# dynacomp.net
KiCad netlist of a schematic drawn in EAGLE
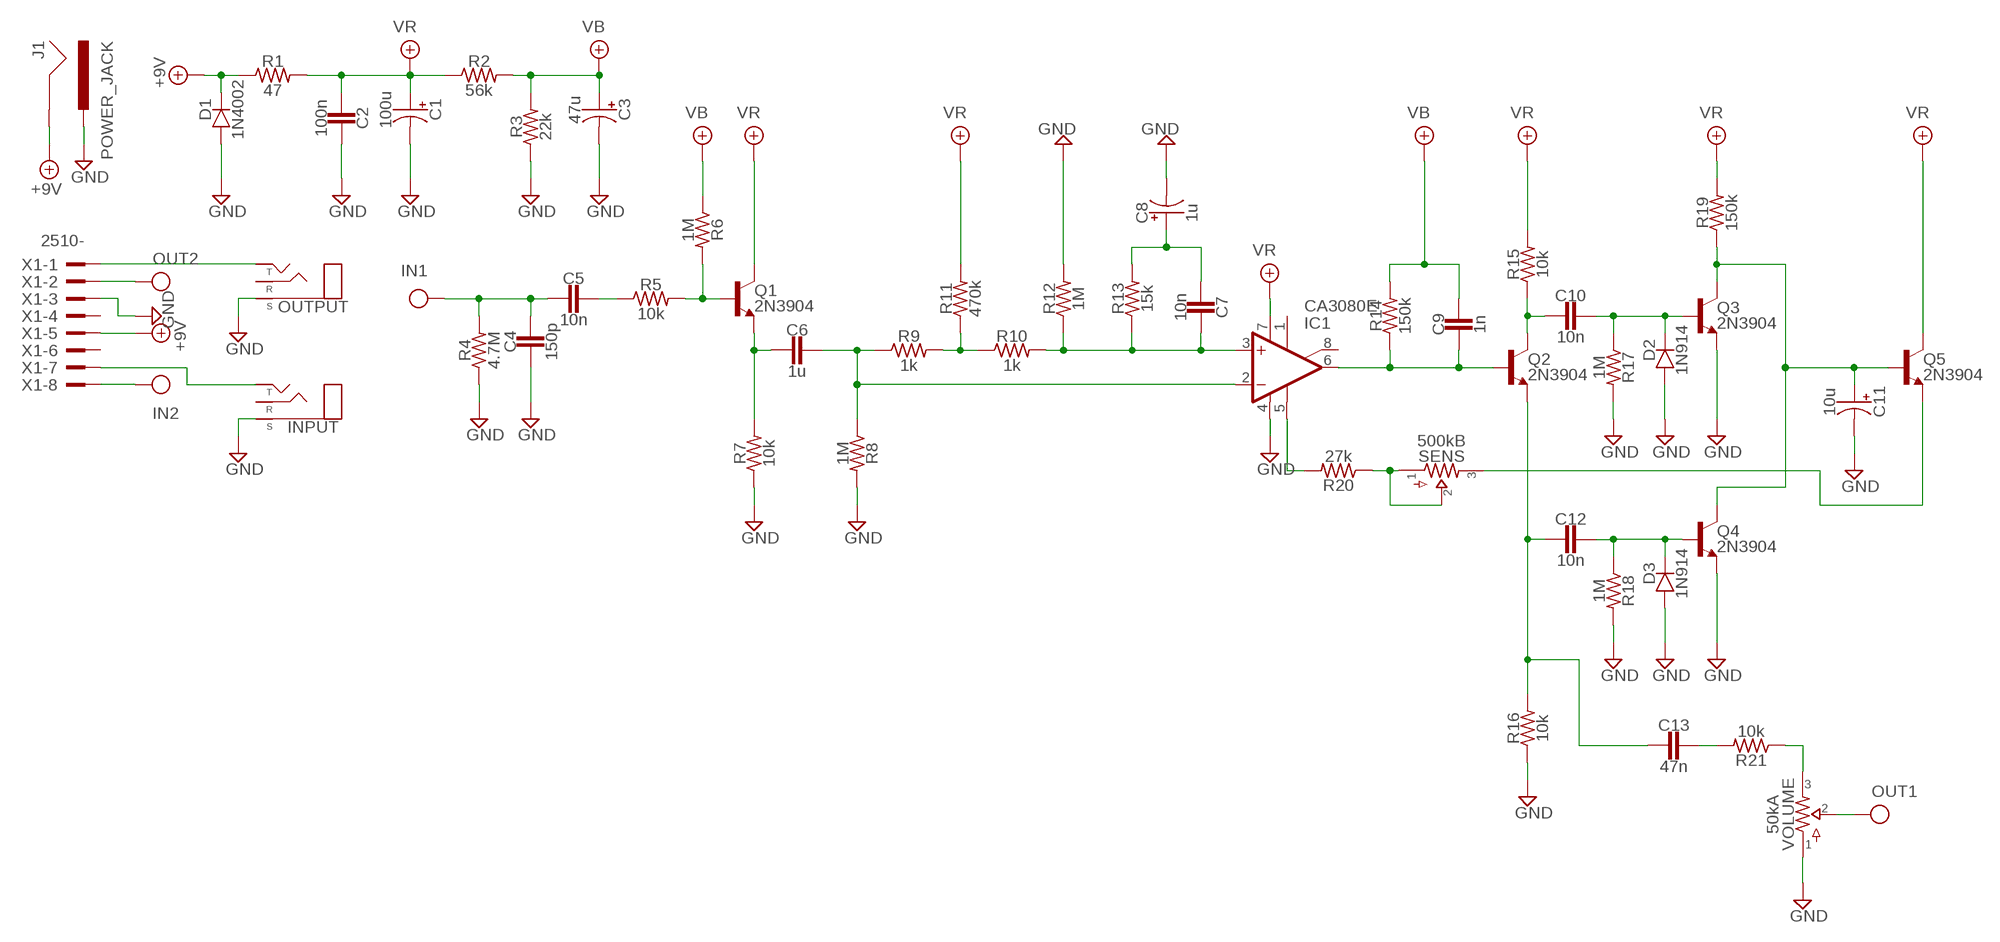
[diagram p0: schematic, sheet 1]

(export (version "E")
  (design (tool "Eeschema 10.0.6"))
  (components
    (comp (ref "C1")
      (value "100u")
      (footprint "eagle-import:040_020")
      (libsource (lib "eagle-import") (part "0400"))
    )
    (comp (ref "C2")
      (value "100n")
      (footprint "eagle-import:050X030_025_2")
      (libsource (lib "eagle-import") (part "CER/FILM2"))
    )
    (comp (ref "C3")
      (value "47u")
      (footprint "eagle-import:040_020")
      (libsource (lib "eagle-import") (part "0400"))
    )
    (comp (ref "C4")
      (value "150p")
      (footprint "eagle-import:050X030_025_2")
      (libsource (lib "eagle-import") (part "CER/FILM2"))
    )
    (comp (ref "C5")
      (value "10n")
      (footprint "eagle-import:BOX_SMALL")
      (libsource (lib "eagle-import") (part "CER/FILMBOX.1"))
    )
    (comp (ref "C6")
      (value "1u")
      (footprint "eagle-import:BOX_BIG")
      (libsource (lib "eagle-import") (part "CER/FILMBOX.3"))
    )
    (comp (ref "C7")
      (value "10n")
      (footprint "eagle-import:BOX_SMALL")
      (libsource (lib "eagle-import") (part "CER/FILMBOX.1"))
    )
    (comp (ref "C8")
      (value "1u")
      (footprint "eagle-import:040_020")
      (libsource (lib "eagle-import") (part "0400"))
    )
    (comp (ref "C9")
      (value "1n")
      (footprint "eagle-import:BOX_SMALL")
      (libsource (lib "eagle-import") (part "CER/FILMBOX.1"))
    )
    (comp (ref "C10")
      (value "10n")
      (footprint "eagle-import:BOX_SMALL")
      (libsource (lib "eagle-import") (part "CER/FILMBOX.1"))
    )
    (comp (ref "C11")
      (value "10u")
      (footprint "eagle-import:040_020")
      (libsource (lib "eagle-import") (part "0400"))
    )
    (comp (ref "C12")
      (value "10n")
      (footprint "eagle-import:BOX_SMALL")
      (libsource (lib "eagle-import") (part "CER/FILMBOX.1"))
    )
    (comp (ref "C13")
      (value "47n")
      (footprint "eagle-import:BOX_SMALL")
      (libsource (lib "eagle-import") (part "CER/FILMBOX.1"))
    )
    (comp (ref "D1")
      (value "1N4002")
      (footprint "eagle-import:DO41-2")
      (libsource (lib "eagle-import") (part "DO41.2"))
    )
    (comp (ref "D2")
      (value "1N914")
      (footprint "eagle-import:DO35-2")
      (libsource (lib "eagle-import") (part "DO35.2"))
    )
    (comp (ref "D3")
      (value "1N914")
      (footprint "eagle-import:DO35-2")
      (libsource (lib "eagle-import") (part "DO35.2"))
    )
    (comp (ref "IC1")
      (value "CA3080E")
      (footprint "eagle-import:DIL08")
      (libsource (lib "eagle-import") (part "3080TH"))
    )
    (comp (ref "INPUT")
      (value "STEREONMJ")
      (footprint "eagle-import:NMJ6HCD2")
      (libsource (lib "eagle-import") (part "STEREONMJ"))
    )
    (comp (ref "J1")
      (value "POWER_JACK")
      (footprint "eagle-import:POWER_JACK_PTH")
      (libsource (lib "eagle-import") (part "POWER_JACK"))
    )
    (comp (ref "OUTPUT")
      (value "STEREONMJ")
      (footprint "eagle-import:NMJ6HCD2")
      (libsource (lib "eagle-import") (part "STEREONMJ"))
    )
    (comp (ref "Q1")
      (value "2N3904")
      (footprint "eagle-import:TO92-")
      (libsource (lib "eagle-import") (part "2N3904"))
    )
    (comp (ref "Q2")
      (value "2N3904")
      (footprint "eagle-import:TO92-")
      (libsource (lib "eagle-import") (part "2N3904"))
    )
    (comp (ref "Q3")
      (value "2N3904")
      (footprint "eagle-import:TO92-")
      (libsource (lib "eagle-import") (part "2N3904"))
    )
    (comp (ref "Q4")
      (value "2N3904")
      (footprint "eagle-import:TO92-")
      (libsource (lib "eagle-import") (part "2N3904"))
    )
    (comp (ref "Q5")
      (value "2N3904")
      (footprint "eagle-import:TO92-")
      (libsource (lib "eagle-import") (part "2N3904"))
    )
    (comp (ref "R1")
      (value "47")
      (footprint "eagle-import:R0207_3")
      (libsource (lib "eagle-import") (part "R_.3B"))
    )
    (comp (ref "R2")
      (value "56k")
      (footprint "eagle-import:R0207_3")
      (libsource (lib "eagle-import") (part "R_.3B"))
    )
    (comp (ref "R3")
      (value "22k")
      (footprint "eagle-import:R0207_3")
      (libsource (lib "eagle-import") (part "R_.3B"))
    )
    (comp (ref "R4")
      (value "4.7M")
      (footprint "eagle-import:R0207_3")
      (libsource (lib "eagle-import") (part "R_.3B"))
    )
    (comp (ref "R5")
      (value "10k")
      (footprint "eagle-import:R0207_3")
      (libsource (lib "eagle-import") (part "R_.3B"))
    )
    (comp (ref "R6")
      (value "1M")
      (footprint "eagle-import:R0207_3")
      (libsource (lib "eagle-import") (part "R_.3B"))
    )
    (comp (ref "R7")
      (value "10k")
      (footprint "eagle-import:R0207_3")
      (libsource (lib "eagle-import") (part "R_.3B"))
    )
    (comp (ref "R8")
      (value "1M")
      (footprint "eagle-import:R0207_3")
      (libsource (lib "eagle-import") (part "R_.3B"))
    )
    (comp (ref "R9")
      (value "1k")
      (footprint "eagle-import:R0207_3")
      (libsource (lib "eagle-import") (part "R_.3B"))
    )
    (comp (ref "R10")
      (value "1k")
      (footprint "eagle-import:R0207_3")
      (libsource (lib "eagle-import") (part "R_.3B"))
    )
    (comp (ref "R11")
      (value "470k")
      (footprint "eagle-import:R0207_3")
      (libsource (lib "eagle-import") (part "R_.3B"))
    )
    (comp (ref "R12")
      (value "1M")
      (footprint "eagle-import:R0207_3")
      (libsource (lib "eagle-import") (part "R_.3B"))
    )
    (comp (ref "R13")
      (value "15k")
      (footprint "eagle-import:R0207_3")
      (libsource (lib "eagle-import") (part "R_.3B"))
    )
    (comp (ref "R14")
      (value "150k")
      (footprint "eagle-import:R0207_3")
      (libsource (lib "eagle-import") (part "R_.3B"))
    )
    (comp (ref "R15")
      (value "10k")
      (footprint "eagle-import:R0207_3")
      (libsource (lib "eagle-import") (part "R_.3B"))
    )
    (comp (ref "R16")
      (value "10k")
      (footprint "eagle-import:R0207_3")
      (libsource (lib "eagle-import") (part "R_.3B"))
    )
    (comp (ref "R17")
      (value "1M")
      (footprint "eagle-import:R0207_3")
      (libsource (lib "eagle-import") (part "R_.3B"))
    )
    (comp (ref "R18")
      (value "1M")
      (footprint "eagle-import:R0207_3")
      (libsource (lib "eagle-import") (part "R_.3B"))
    )
    (comp (ref "R19")
      (value "150k")
      (footprint "eagle-import:R0207_3")
      (libsource (lib "eagle-import") (part "R_.3B"))
    )
    (comp (ref "R20")
      (value "27k")
      (footprint "eagle-import:R0207_3")
      (libsource (lib "eagle-import") (part "R_.3B"))
    )
    (comp (ref "R21")
      (value "10k")
      (footprint "eagle-import:R0207_3")
      (libsource (lib "eagle-import") (part "R_.3B"))
    )
    (comp (ref "SENS")
      (value "500kB")
      (footprint "eagle-import:16MM")
      (libsource (lib "eagle-import") (part "POTS16MM"))
    )
    (comp (ref "VOLUME")
      (value "50kA")
      (footprint "eagle-import:16MM")
      (libsource (lib "eagle-import") (part "POTS16MM"))
    )
    (comp (ref "X1")
      (value "2510-")
      (footprint "eagle-import:PAK100_2500-10")
      (fields (field (name "MF") "3M") (field (name "MPN") "2510-6002UB"))
      (libsource (lib "eagle-import") (part "2510-"))
    )
  )
  (nets
    (net (code "1") (name "+9V") (class "Default")
      (node (ref "D1") (pin "C") (pinfunction "C_C") (pintype "passive"))
      (node (ref "J1") (pin "GND") (pinfunction "GND_GND") (pintype "bidirectional"))
      (node (ref "R1") (pin "1") (pinfunction "1_1") (pintype "passive"))
      (node (ref "X1") (pin "5") (pinfunction "KL_5") (pintype "passive"))
    )
    (net (code "2") (name "GND") (class "Default")
      (node (ref "C1") (pin "-") (pinfunction "-_-") (pintype "passive"))
      (node (ref "C11") (pin "-") (pinfunction "-_-") (pintype "passive"))
      (node (ref "C2") (pin "1") (pinfunction "1_1") (pintype "passive"))
      (node (ref "C3") (pin "-") (pinfunction "-_-") (pintype "passive"))
      (node (ref "C4") (pin "2") (pinfunction "2_2") (pintype "passive"))
      (node (ref "C8") (pin "-") (pinfunction "-_-") (pintype "passive"))
      (node (ref "D1") (pin "A") (pinfunction "A_A") (pintype "passive"))
      (node (ref "D2") (pin "A") (pinfunction "A_A") (pintype "passive"))
      (node (ref "D3") (pin "A") (pinfunction "A_A") (pintype "passive"))
      (node (ref "IC1") (pin "4") (pinfunction "V-_4") (pintype "power_in"))
      (node (ref "INPUT") (pin "S") (pinfunction "S_S") (pintype "passive"))
      (node (ref "J1") (pin "PWR") (pinfunction "PWR_PWR") (pintype "bidirectional"))
      (node (ref "OUTPUT") (pin "S") (pinfunction "S_S") (pintype "passive"))
      (node (ref "Q3") (pin "3") (pinfunction "E_3") (pintype "passive"))
      (node (ref "Q4") (pin "3") (pinfunction "E_3") (pintype "passive"))
      (node (ref "R12") (pin "2") (pinfunction "2_2") (pintype "passive"))
      (node (ref "R16") (pin "1") (pinfunction "1_1") (pintype "passive"))
      (node (ref "R17") (pin "2") (pinfunction "2_2") (pintype "passive"))
      (node (ref "R18") (pin "2") (pinfunction "2_2") (pintype "passive"))
      (node (ref "R3") (pin "1") (pinfunction "1_1") (pintype "passive"))
      (node (ref "R4") (pin "1") (pinfunction "1_1") (pintype "passive"))
      (node (ref "R7") (pin "1") (pinfunction "1_1") (pintype "passive"))
      (node (ref "R8") (pin "2") (pinfunction "2_2") (pintype "passive"))
      (node (ref "VOLUME") (pin "1") (pinfunction "1_1") (pintype "passive"))
      (node (ref "X1") (pin "3") (pinfunction "KL_3") (pintype "passive"))
    )
    (net (code "3") (name "IN") (class "Default")
      (node (ref "C4") (pin "1") (pinfunction "1_1") (pintype "passive"))
      (node (ref "C5") (pin "2") (pinfunction "2_2") (pintype "passive"))
      (node (ref "R4") (pin "2") (pinfunction "2_2") (pintype "passive"))
      (node (ref "X1") (pin "8") (pinfunction "KL_8") (pintype "passive"))
    )
    (net (code "4") (name "Net-(C5-Pad1)") (class "Default")
      (node (ref "C5") (pin "1") (pinfunction "1_1") (pintype "passive"))
      (node (ref "R5") (pin "1") (pinfunction "1_1") (pintype "passive"))
    )
    (net (code "5") (name "Net-(C7-Pad2)") (class "Default")
      (node (ref "C7") (pin "2") (pinfunction "2_2") (pintype "passive"))
      (node (ref "C8") (pin "+") (pinfunction "+_+") (pintype "passive"))
      (node (ref "R13") (pin "2") (pinfunction "2_2") (pintype "passive"))
    )
    (net (code "6") (name "Net-(C13-Pad1)") (class "Default")
      (node (ref "C13") (pin "1") (pinfunction "1_1") (pintype "passive"))
      (node (ref "R21") (pin "2") (pinfunction "2_2") (pintype "passive"))
    )
    (net (code "7") (name "Net-(IC1-+IN)") (class "Default")
      (node (ref "C7") (pin "1") (pinfunction "1_1") (pintype "passive"))
      (node (ref "IC1") (pin "3") (pinfunction "+IN_3") (pintype "input"))
      (node (ref "R10") (pin "2") (pinfunction "2_2") (pintype "passive"))
      (node (ref "R12") (pin "1") (pinfunction "1_1") (pintype "passive"))
      (node (ref "R13") (pin "1") (pinfunction "1_1") (pintype "passive"))
    )
    (net (code "8") (name "Net-(IC1--IN)") (class "Default")
      (node (ref "C6") (pin "1") (pinfunction "1_1") (pintype "passive"))
      (node (ref "IC1") (pin "2") (pinfunction "-IN_2") (pintype "input"))
      (node (ref "R8") (pin "1") (pinfunction "1_1") (pintype "passive"))
      (node (ref "R9") (pin "1") (pinfunction "1_1") (pintype "passive"))
    )
    (net (code "9") (name "Net-(IC1-OPT)") (class "Default")
      (node (ref "IC1") (pin "5") (pinfunction "OPT_5") (pintype "passive"))
      (node (ref "R20") (pin "2") (pinfunction "2_2") (pintype "passive"))
    )
    (net (code "10") (name "Net-(IC1-OUT)") (class "Default")
      (node (ref "C9") (pin "2") (pinfunction "2_2") (pintype "passive"))
      (node (ref "IC1") (pin "6") (pinfunction "OUT_6") (pintype "output"))
      (node (ref "Q2") (pin "2") (pinfunction "B_2") (pintype "passive"))
      (node (ref "R14") (pin "1") (pinfunction "1_1") (pintype "passive"))
    )
    (net (code "11") (name "Net-(Q1-B)") (class "Default")
      (node (ref "Q1") (pin "2") (pinfunction "B_2") (pintype "passive"))
      (node (ref "R5") (pin "2") (pinfunction "2_2") (pintype "passive"))
      (node (ref "R6") (pin "2") (pinfunction "2_2") (pintype "passive"))
    )
    (net (code "12") (name "Net-(Q1-E)") (class "Default")
      (node (ref "C6") (pin "2") (pinfunction "2_2") (pintype "passive"))
      (node (ref "Q1") (pin "3") (pinfunction "E_3") (pintype "passive"))
      (node (ref "R7") (pin "2") (pinfunction "2_2") (pintype "passive"))
    )
    (net (code "13") (name "Net-(Q2-C)") (class "Default")
      (node (ref "C10") (pin "2") (pinfunction "2_2") (pintype "passive"))
      (node (ref "Q2") (pin "1") (pinfunction "C_1") (pintype "passive"))
      (node (ref "R15") (pin "1") (pinfunction "1_1") (pintype "passive"))
    )
    (net (code "14") (name "Net-(Q2-E)") (class "Default")
      (node (ref "C12") (pin "2") (pinfunction "2_2") (pintype "passive"))
      (node (ref "C13") (pin "2") (pinfunction "2_2") (pintype "passive"))
      (node (ref "Q2") (pin "3") (pinfunction "E_3") (pintype "passive"))
      (node (ref "R16") (pin "2") (pinfunction "2_2") (pintype "passive"))
    )
    (net (code "15") (name "Net-(Q3-B)") (class "Default")
      (node (ref "C10") (pin "1") (pinfunction "1_1") (pintype "passive"))
      (node (ref "D2") (pin "C") (pinfunction "C_C") (pintype "passive"))
      (node (ref "Q3") (pin "2") (pinfunction "B_2") (pintype "passive"))
      (node (ref "R17") (pin "1") (pinfunction "1_1") (pintype "passive"))
    )
    (net (code "16") (name "Net-(Q3-C)") (class "Default")
      (node (ref "C11") (pin "+") (pinfunction "+_+") (pintype "passive"))
      (node (ref "Q3") (pin "1") (pinfunction "C_1") (pintype "passive"))
      (node (ref "Q4") (pin "1") (pinfunction "C_1") (pintype "passive"))
      (node (ref "Q5") (pin "2") (pinfunction "B_2") (pintype "passive"))
      (node (ref "R19") (pin "1") (pinfunction "1_1") (pintype "passive"))
    )
    (net (code "17") (name "Net-(Q4-B)") (class "Default")
      (node (ref "C12") (pin "1") (pinfunction "1_1") (pintype "passive"))
      (node (ref "D3") (pin "C") (pinfunction "C_C") (pintype "passive"))
      (node (ref "Q4") (pin "2") (pinfunction "B_2") (pintype "passive"))
      (node (ref "R18") (pin "1") (pinfunction "1_1") (pintype "passive"))
    )
    (net (code "18") (name "Net-(Q5-E)") (class "Default")
      (node (ref "Q5") (pin "3") (pinfunction "E_3") (pintype "passive"))
      (node (ref "SENS") (pin "3") (pinfunction "3_3") (pintype "passive"))
    )
    (net (code "19") (name "Net-(R10-Pad1)") (class "Default")
      (node (ref "R10") (pin "1") (pinfunction "1_1") (pintype "passive"))
      (node (ref "R11") (pin "1") (pinfunction "1_1") (pintype "passive"))
      (node (ref "R9") (pin "2") (pinfunction "2_2") (pintype "passive"))
    )
    (net (code "20") (name "Net-(R20-Pad1)") (class "Default")
      (node (ref "R20") (pin "1") (pinfunction "1_1") (pintype "passive"))
      (node (ref "SENS") (pin "1") (pinfunction "1_1") (pintype "passive"))
      (node (ref "SENS") (pin "2") (pinfunction "2_2") (pintype "passive"))
    )
    (net (code "21") (name "Net-(R21-Pad1)") (class "Default")
      (node (ref "R21") (pin "1") (pinfunction "1_1") (pintype "passive"))
      (node (ref "VOLUME") (pin "3") (pinfunction "3_3") (pintype "passive"))
    )
    (net (code "22") (name "Net-(X1A-KL)") (class "Default")
      (node (ref "OUTPUT") (pin "T") (pinfunction "T_T") (pintype "passive"))
      (node (ref "X1") (pin "1") (pinfunction "KL_1") (pintype "passive"))
    )
    (net (code "23") (name "Net-(X1G-KL)") (class "Default")
      (node (ref "INPUT") (pin "T") (pinfunction "T_T") (pintype "passive"))
      (node (ref "X1") (pin "7") (pinfunction "KL_7") (pintype "passive"))
    )
    (net (code "24") (name "OUT") (class "Default")
      (node (ref "VOLUME") (pin "2") (pinfunction "2_2") (pintype "passive"))
      (node (ref "X1") (pin "2") (pinfunction "KL_2") (pintype "passive"))
    )
    (net (code "25") (name "VB") (class "Default")
      (node (ref "C3") (pin "+") (pinfunction "+_+") (pintype "passive"))
      (node (ref "C9") (pin "1") (pinfunction "1_1") (pintype "passive"))
      (node (ref "R14") (pin "2") (pinfunction "2_2") (pintype "passive"))
      (node (ref "R2") (pin "2") (pinfunction "2_2") (pintype "passive"))
      (node (ref "R3") (pin "2") (pinfunction "2_2") (pintype "passive"))
      (node (ref "R6") (pin "1") (pinfunction "1_1") (pintype "passive"))
    )
    (net (code "26") (name "VR") (class "Default")
      (node (ref "C1") (pin "+") (pinfunction "+_+") (pintype "passive"))
      (node (ref "C2") (pin "2") (pinfunction "2_2") (pintype "passive"))
      (node (ref "IC1") (pin "7") (pinfunction "V+_7") (pintype "power_in"))
      (node (ref "Q1") (pin "1") (pinfunction "C_1") (pintype "passive"))
      (node (ref "Q5") (pin "1") (pinfunction "C_1") (pintype "passive"))
      (node (ref "R1") (pin "2") (pinfunction "2_2") (pintype "passive"))
      (node (ref "R11") (pin "2") (pinfunction "2_2") (pintype "passive"))
      (node (ref "R15") (pin "2") (pinfunction "2_2") (pintype "passive"))
      (node (ref "R19") (pin "2") (pinfunction "2_2") (pintype "passive"))
      (node (ref "R2") (pin "1") (pinfunction "1_1") (pintype "passive"))
    )
    (net (code "27") (name "unconnected-(IC1-ON1-Pad1)") (class "Default")
      (node (ref "IC1") (pin "1") (pinfunction "ON1_1") (pintype "passive"))
    )
    (net (code "28") (name "unconnected-(IC1-ON2-Pad8)") (class "Default")
      (node (ref "IC1") (pin "8") (pinfunction "ON2_8") (pintype "passive"))
    )
    (net (code "29") (name "unconnected-(INPUT-PadR)") (class "Default")
      (node (ref "INPUT") (pin "R") (pinfunction "R_R") (pintype "passive"))
    )
    (net (code "30") (name "unconnected-(OUTPUT-PadR)") (class "Default")
      (node (ref "OUTPUT") (pin "R") (pinfunction "R_R") (pintype "passive"))
    )
    (net (code "31") (name "unconnected-(X1D-KL-Pad4)") (class "Default")
      (node (ref "X1") (pin "4") (pinfunction "KL_4") (pintype "passive"))
    )
    (net (code "32") (name "unconnected-(X1F-KL-Pad6)") (class "Default")
      (node (ref "X1") (pin "6") (pinfunction "KL_6") (pintype "passive"))
    )
  )
)
